# 467444_130_3_5-A.net
KiCad netlist of a schematic drawn in Altium Designer
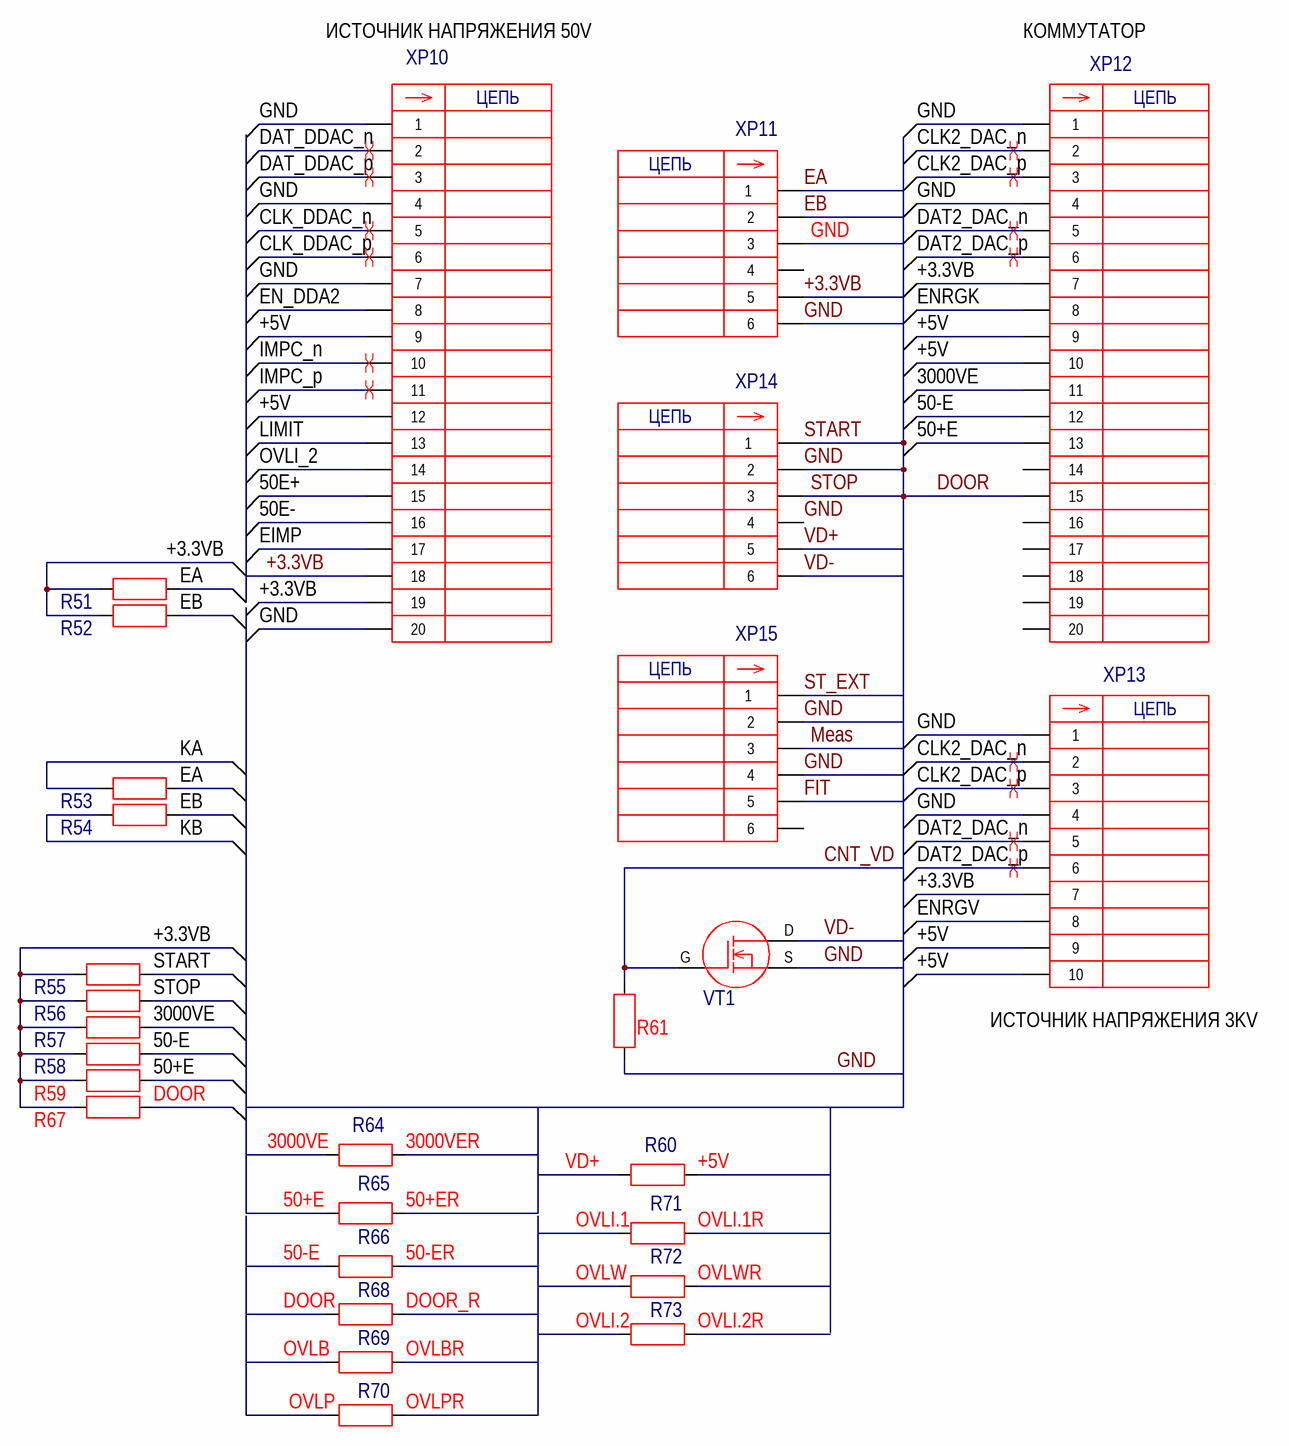
[diagram p0: УШЯИ.467444.130Э3_5-A.SchDoc]

(export (version "E")
  (design (tool "Eeschema 10.0.6"))
  (components
    (comp (ref "R51")
      (value "10k")
      (footprint "R_0805 [2012 Metric]")
      (fields (field (name "TOLERANCE") "±1%"))
      (libsource (lib "lib") (part "R_Const"))
    )
    (comp (ref "R52")
      (value "10k")
      (footprint "R_0805 [2012 Metric]")
      (fields (field (name "TOLERANCE") "±1%"))
      (libsource (lib "lib") (part "R_Const"))
    )
    (comp (ref "R53")
      (value "10k")
      (footprint "R_0805 [2012 Metric]")
      (fields (field (name "TOLERANCE") "±1%"))
      (libsource (lib "lib") (part "R_Const"))
    )
    (comp (ref "R54")
      (value "10k")
      (footprint "R_0805 [2012 Metric]")
      (fields (field (name "TOLERANCE") "±1%"))
      (libsource (lib "lib") (part "R_Const"))
    )
    (comp (ref "R55")
      (value "10k")
      (footprint "R_0805 [2012 Metric]")
      (fields (field (name "TOLERANCE") "±1%"))
      (libsource (lib "lib") (part "R_Const"))
    )
    (comp (ref "R56")
      (value "10k")
      (footprint "R_0805 [2012 Metric]")
      (fields (field (name "TOLERANCE") "±1%"))
      (libsource (lib "lib") (part "R_Const"))
    )
    (comp (ref "R57")
      (value "10k")
      (footprint "R_0805 [2012 Metric]")
      (fields (field (name "TOLERANCE") "±1%"))
      (libsource (lib "lib") (part "R_Const"))
    )
    (comp (ref "R58")
      (value "10k")
      (footprint "R_0805 [2012 Metric]")
      (fields (field (name "TOLERANCE") "±1%"))
      (libsource (lib "lib") (part "R_Const"))
    )
    (comp (ref "R59")
      (value "10k")
      (footprint "R_0805 [2012 Metric]")
      (fields (field (name "TOLERANCE") "±1%"))
      (libsource (lib "lib") (part "R_Const"))
    )
    (comp (ref "R60")
      (value "10k")
      (footprint "R_0805 [2012 Metric]")
      (fields (field (name "TOLERANCE") "±1%"))
      (libsource (lib "lib") (part "R_Const"))
    )
    (comp (ref "R61")
      (value "10k")
      (footprint "R_1206 [3216 Metric]")
      (fields (field (name "TOLERANCE") "±5%"))
      (libsource (lib "Lib_MN") (part "R_Const"))
    )
    (comp (ref "R64")
      (value "10k")
      (footprint "R_0805 [2012 Metric]")
      (fields (field (name "TOLERANCE") "±1%"))
      (libsource (lib "lib") (part "R_Const"))
    )
    (comp (ref "R65")
      (value "10k")
      (footprint "R_0805 [2012 Metric]")
      (fields (field (name "TOLERANCE") "±1%"))
      (libsource (lib "lib") (part "R_Const"))
    )
    (comp (ref "R66")
      (value "10k")
      (footprint "R_0805 [2012 Metric]")
      (fields (field (name "TOLERANCE") "±1%"))
      (libsource (lib "lib") (part "R_Const"))
    )
    (comp (ref "R67")
      (value "10k")
      (footprint "R_0805 [2012 Metric]")
      (fields (field (name "TOLERANCE") "±1%"))
      (libsource (lib "lib") (part "R_Const"))
    )
    (comp (ref "R68")
      (value "10k")
      (footprint "R_0805 [2012 Metric]")
      (fields (field (name "TOLERANCE") "±1%"))
      (libsource (lib "lib") (part "R_Const"))
    )
    (comp (ref "R69")
      (value "10k")
      (footprint "R_0805 [2012 Metric]")
      (fields (field (name "TOLERANCE") "±1%"))
      (libsource (lib "lib") (part "R_Const"))
    )
    (comp (ref "R70")
      (value "10k")
      (footprint "R_0805 [2012 Metric]")
      (fields (field (name "TOLERANCE") "±1%"))
      (libsource (lib "lib") (part "R_Const"))
    )
    (comp (ref "R71")
      (value "10k")
      (footprint "R_0805 [2012 Metric]")
      (fields (field (name "TOLERANCE") "±1%"))
      (libsource (lib "lib") (part "R_Const"))
    )
    (comp (ref "R72")
      (value "10k")
      (footprint "R_0805 [2012 Metric]")
      (fields (field (name "TOLERANCE") "±1%"))
      (libsource (lib "lib") (part "R_Const"))
    )
    (comp (ref "R73")
      (value "10k")
      (footprint "R_0805 [2012 Metric]")
      (fields (field (name "TOLERANCE") "±1%"))
      (libsource (lib "lib") (part "R_Const"))
    )
    (comp (ref "VT1")
      (value "NDS7002A")
      (footprint "SOT-23-3_[TO-236AB]_Transistor_n")
      (description "Транзистор n-канальный, изолированный затвор")
      (fields (field (name "MANUFACTURER") "Onsemi"))
      (libsource (lib "Lib_MN") (part "n-channel"))
    )
    (comp (ref "XP10")
      (value "BH2-20R")
      (footprint "BH2-20R")
      (description "Male, 20 pins, 2 rows, Right Angle, DS1014-20RF1B-B, 2 mm")
      (fields (field (name "MANUFACTURER") "Connfly electronic"))
      (libsource (lib "lib") (part "M_20"))
    )
    (comp (ref "XP11")
      (value "AMPMODU II 280372-2")
      (footprint "AMP II-280372-2")
      (description "Male, 6 pin, 1 row, Vertical, Board-to-Board, 2.54 mm")
      (fields (field (name "MANUFACTURER") "TE Connectivity"))
      (libsource (lib "Lib_MN") (part "M_6"))
    )
    (comp (ref "XP12")
      (value "BH2-20R")
      (footprint "BH2-20R")
      (description "Male, 20 pins, 2 rows, Right Angle, DS1014-20RF1B-B, 2 mm")
      (fields (field (name "MANUFACTURER") "Connfly electronic"))
      (libsource (lib "lib") (part "M_20"))
    )
    (comp (ref "XP13")
      (value "BH2-10R")
      (footprint "BH2-10R")
      (description "Male, 10 pins, 2 rows, Vertical, DS1014-10RF1B-B, 2 mm")
      (fields (field (name "MANUFACTURER") "Connfly electronic"))
      (libsource (lib "lib") (part "M_10"))
    )
    (comp (ref "XP14")
      (value "AMPMODU II 280372-2")
      (footprint "AMP II-280372-2")
      (description "Male, 6 pin, 1 row, Vertical, Board-to-Board, 2.54 mm")
      (fields (field (name "MANUFACTURER") "TE Connectivity"))
      (libsource (lib "Lib_MN") (part "M_6"))
    )
    (comp (ref "XP15")
      (value "AMPMODU II 280372-2")
      (footprint "AMP II-280372-2")
      (description "Male, 6 pin, 1 row, Vertical, Board-to-Board, 2.54 mm")
      (fields (field (name "MANUFACTURER") "TE Connectivity"))
      (libsource (lib "Lib_MN") (part "M_6"))
    )
  )
  (nets
    (net (code "1") (name "/+3.3VB") (class "Default")
      (node (ref "R51") (pin "1") (pinfunction "1_1") (pintype "passive"))
      (node (ref "R52") (pin "1") (pinfunction "1_1") (pintype "passive"))
      (node (ref "R55") (pin "1") (pinfunction "1_1") (pintype "passive"))
      (node (ref "R56") (pin "1") (pinfunction "1_1") (pintype "passive"))
      (node (ref "R57") (pin "1") (pinfunction "1_1") (pintype "passive"))
      (node (ref "R58") (pin "1") (pinfunction "1_1") (pintype "passive"))
      (node (ref "R59") (pin "1") (pinfunction "1_1") (pintype "passive"))
      (node (ref "R67") (pin "1") (pinfunction "1_1") (pintype "passive"))
      (node (ref "XP10") (pin "18") (pinfunction "18_18") (pintype "passive"))
      (node (ref "XP10") (pin "19") (pinfunction "19_19") (pintype "passive"))
      (node (ref "XP11") (pin "5") (pinfunction "5_5") (pintype "passive"))
      (node (ref "XP12") (pin "7") (pinfunction "7_7") (pintype "passive"))
      (node (ref "XP13") (pin "7") (pinfunction "7_7") (pintype "passive"))
    )
    (net (code "2") (name "/+5V") (class "Default")
      (node (ref "R60") (pin "2") (pinfunction "2_2") (pintype "passive"))
      (node (ref "XP10") (pin "12") (pinfunction "12_12") (pintype "passive"))
      (node (ref "XP10") (pin "9") (pinfunction "9_9") (pintype "passive"))
      (node (ref "XP12") (pin "10") (pinfunction "10_10") (pintype "passive"))
      (node (ref "XP12") (pin "9") (pinfunction "9_9") (pintype "passive"))
      (node (ref "XP13") (pin "10") (pinfunction "10_10") (pintype "passive"))
      (node (ref "XP13") (pin "9") (pinfunction "9_9") (pintype "passive"))
    )
    (net (code "3") (name "/50+E") (class "Default")
      (node (ref "R59") (pin "2") (pinfunction "2_2") (pintype "passive"))
      (node (ref "R65") (pin "1") (pinfunction "1_1") (pintype "passive"))
      (node (ref "XP12") (pin "13") (pinfunction "13_13") (pintype "passive"))
    )
    (net (code "4") (name "/50+ER") (class "Default")
      (node (ref "R65") (pin "2") (pinfunction "2_2") (pintype "passive"))
    )
    (net (code "5") (name "/50-E") (class "Default")
      (node (ref "R58") (pin "2") (pinfunction "2_2") (pintype "passive"))
      (node (ref "R66") (pin "1") (pinfunction "1_1") (pintype "passive"))
      (node (ref "XP12") (pin "12") (pinfunction "12_12") (pintype "passive"))
    )
    (net (code "6") (name "/50-ER") (class "Default")
      (node (ref "R66") (pin "2") (pinfunction "2_2") (pintype "passive"))
    )
    (net (code "7") (name "/50E+") (class "Default")
      (node (ref "XP10") (pin "15") (pinfunction "15_15") (pintype "passive"))
    )
    (net (code "8") (name "/50E-") (class "Default")
      (node (ref "XP10") (pin "16") (pinfunction "16_16") (pintype "passive"))
    )
    (net (code "9") (name "/3000VE") (class "Default")
      (node (ref "R57") (pin "2") (pinfunction "2_2") (pintype "passive"))
      (node (ref "R64") (pin "1") (pinfunction "1_1") (pintype "passive"))
      (node (ref "XP12") (pin "11") (pinfunction "11_11") (pintype "passive"))
    )
    (net (code "10") (name "/3000VER") (class "Default")
      (node (ref "R64") (pin "2") (pinfunction "2_2") (pintype "passive"))
    )
    (net (code "11") (name "/CLK2_DAC_n") (class "Default")
      (node (ref "XP12") (pin "2") (pinfunction "2_2") (pintype "passive"))
      (node (ref "XP13") (pin "2") (pinfunction "2_2") (pintype "passive"))
    )
    (net (code "12") (name "/CLK2_DAC_p") (class "Default")
      (node (ref "XP12") (pin "3") (pinfunction "3_3") (pintype "passive"))
      (node (ref "XP13") (pin "3") (pinfunction "3_3") (pintype "passive"))
    )
    (net (code "13") (name "/CLK_DDAC_n") (class "Default")
      (node (ref "XP10") (pin "5") (pinfunction "5_5") (pintype "passive"))
    )
    (net (code "14") (name "/CLK_DDAC_p") (class "Default")
      (node (ref "XP10") (pin "6") (pinfunction "6_6") (pintype "passive"))
    )
    (net (code "15") (name "/CNT_VD") (class "Default")
      (node (ref "R61") (pin "2") (pinfunction "2_2") (pintype "passive"))
      (node (ref "VT1") (pin "G") (pinfunction "З_G") (pintype "passive"))
    )
    (net (code "16") (name "/DAT2_DAC_n") (class "Default")
      (node (ref "XP12") (pin "5") (pinfunction "5_5") (pintype "passive"))
      (node (ref "XP13") (pin "5") (pinfunction "5_5") (pintype "passive"))
    )
    (net (code "17") (name "/DAT2_DAC_p") (class "Default")
      (node (ref "XP12") (pin "6") (pinfunction "6_6") (pintype "passive"))
      (node (ref "XP13") (pin "6") (pinfunction "6_6") (pintype "passive"))
    )
    (net (code "18") (name "/DAT_DDAC_n") (class "Default")
      (node (ref "XP10") (pin "2") (pinfunction "2_2") (pintype "passive"))
    )
    (net (code "19") (name "/DAT_DDAC_p") (class "Default")
      (node (ref "XP10") (pin "3") (pinfunction "3_3") (pintype "passive"))
    )
    (net (code "20") (name "/DOOR") (class "Default")
      (node (ref "R55") (pin "2") (pinfunction "2_2") (pintype "passive"))
      (node (ref "R56") (pin "2") (pinfunction "2_2") (pintype "passive"))
      (node (ref "R61") (pin "1") (pinfunction "1_1") (pintype "passive"))
      (node (ref "R67") (pin "2") (pinfunction "2_2") (pintype "passive"))
      (node (ref "R68") (pin "1") (pinfunction "1_1") (pintype "passive"))
      (node (ref "VT1") (pin "S") (pinfunction "И_S") (pintype "passive"))
      (node (ref "XP10") (pin "1") (pinfunction "1_1") (pintype "passive"))
      (node (ref "XP10") (pin "20") (pinfunction "20_20") (pintype "passive"))
      (node (ref "XP10") (pin "4") (pinfunction "4_4") (pintype "passive"))
      (node (ref "XP10") (pin "7") (pinfunction "7_7") (pintype "passive"))
      (node (ref "XP11") (pin "3") (pinfunction "3_3") (pintype "passive"))
      (node (ref "XP11") (pin "6") (pinfunction "6_6") (pintype "passive"))
      (node (ref "XP12") (pin "1") (pinfunction "1_1") (pintype "passive"))
      (node (ref "XP12") (pin "15") (pinfunction "15_15") (pintype "passive"))
      (node (ref "XP12") (pin "4") (pinfunction "4_4") (pintype "passive"))
      (node (ref "XP13") (pin "1") (pinfunction "1_1") (pintype "passive"))
      (node (ref "XP13") (pin "4") (pinfunction "4_4") (pintype "passive"))
      (node (ref "XP14") (pin "1") (pinfunction "1_1") (pintype "passive"))
      (node (ref "XP14") (pin "2") (pinfunction "2_2") (pintype "passive"))
      (node (ref "XP14") (pin "3") (pinfunction "3_3") (pintype "passive"))
      (node (ref "XP14") (pin "4") (pinfunction "4_4") (pintype "passive"))
      (node (ref "XP15") (pin "2") (pinfunction "2_2") (pintype "passive"))
      (node (ref "XP15") (pin "4") (pinfunction "4_4") (pintype "passive"))
    )
    (net (code "21") (name "/DOOR_R") (class "Default")
      (node (ref "R68") (pin "2") (pinfunction "2_2") (pintype "passive"))
    )
    (net (code "22") (name "/EA") (class "Default")
      (node (ref "R51") (pin "2") (pinfunction "2_2") (pintype "passive"))
      (node (ref "R53") (pin "2") (pinfunction "2_2") (pintype "passive"))
      (node (ref "XP11") (pin "1") (pinfunction "1_1") (pintype "passive"))
    )
    (net (code "23") (name "/EB") (class "Default")
      (node (ref "R52") (pin "2") (pinfunction "2_2") (pintype "passive"))
      (node (ref "R54") (pin "2") (pinfunction "2_2") (pintype "passive"))
      (node (ref "XP11") (pin "2") (pinfunction "2_2") (pintype "passive"))
    )
    (net (code "24") (name "/EIMP") (class "Default")
      (node (ref "XP10") (pin "17") (pinfunction "17_17") (pintype "passive"))
    )
    (net (code "25") (name "/ENRGK") (class "Default")
      (node (ref "XP12") (pin "8") (pinfunction "8_8") (pintype "passive"))
    )
    (net (code "26") (name "/ENRGV") (class "Default")
      (node (ref "XP13") (pin "8") (pinfunction "8_8") (pintype "passive"))
    )
    (net (code "27") (name "/EN_DDA2") (class "Default")
      (node (ref "XP10") (pin "8") (pinfunction "8_8") (pintype "passive"))
    )
    (net (code "28") (name "/FIT") (class "Default")
      (node (ref "XP15") (pin "5") (pinfunction "5_5") (pintype "passive"))
    )
    (net (code "29") (name "/IMPC_n") (class "Default")
      (node (ref "XP10") (pin "10") (pinfunction "10_10") (pintype "passive"))
    )
    (net (code "30") (name "/IMPC_p") (class "Default")
      (node (ref "XP10") (pin "11") (pinfunction "11_11") (pintype "passive"))
    )
    (net (code "31") (name "/KA") (class "Default")
      (node (ref "R53") (pin "1") (pinfunction "1_1") (pintype "passive"))
    )
    (net (code "32") (name "/KB") (class "Default")
      (node (ref "R54") (pin "1") (pinfunction "1_1") (pintype "passive"))
    )
    (net (code "33") (name "/LIMIT") (class "Default")
      (node (ref "XP10") (pin "13") (pinfunction "13_13") (pintype "passive"))
    )
    (net (code "34") (name "/Meas") (class "Default")
      (node (ref "XP15") (pin "3") (pinfunction "3_3") (pintype "passive"))
    )
    (net (code "35") (name "/OVLB") (class "Default")
      (node (ref "R69") (pin "1") (pinfunction "1_1") (pintype "passive"))
    )
    (net (code "36") (name "/OVLBR") (class "Default")
      (node (ref "R69") (pin "2") (pinfunction "2_2") (pintype "passive"))
    )
    (net (code "37") (name "/OVLI.1") (class "Default")
      (node (ref "R71") (pin "1") (pinfunction "1_1") (pintype "passive"))
    )
    (net (code "38") (name "/OVLI.1R") (class "Default")
      (node (ref "R71") (pin "2") (pinfunction "2_2") (pintype "passive"))
    )
    (net (code "39") (name "/OVLI.2") (class "Default")
      (node (ref "R73") (pin "1") (pinfunction "1_1") (pintype "passive"))
    )
    (net (code "40") (name "/OVLI.2R") (class "Default")
      (node (ref "R73") (pin "2") (pinfunction "2_2") (pintype "passive"))
    )
    (net (code "41") (name "/OVLI_2") (class "Default")
      (node (ref "XP10") (pin "14") (pinfunction "14_14") (pintype "passive"))
    )
    (net (code "42") (name "/OVLP") (class "Default")
      (node (ref "R70") (pin "1") (pinfunction "1_1") (pintype "passive"))
    )
    (net (code "43") (name "/OVLPR") (class "Default")
      (node (ref "R70") (pin "2") (pinfunction "2_2") (pintype "passive"))
    )
    (net (code "44") (name "/OVLW") (class "Default")
      (node (ref "R72") (pin "1") (pinfunction "1_1") (pintype "passive"))
    )
    (net (code "45") (name "/OVLWR") (class "Default")
      (node (ref "R72") (pin "2") (pinfunction "2_2") (pintype "passive"))
    )
    (net (code "46") (name "/ST_EXT") (class "Default")
      (node (ref "XP15") (pin "1") (pinfunction "1_1") (pintype "passive"))
    )
    (net (code "47") (name "/VD+") (class "Default")
      (node (ref "R60") (pin "1") (pinfunction "1_1") (pintype "passive"))
      (node (ref "XP14") (pin "5") (pinfunction "5_5") (pintype "passive"))
    )
    (net (code "48") (name "/VD-") (class "Default")
      (node (ref "VT1") (pin "D") (pinfunction "C_D") (pintype "passive"))
      (node (ref "XP14") (pin "6") (pinfunction "6_6") (pintype "passive"))
    )
    (net (code "49") (name "unconnected-(XP11-Pad4)") (class "Default")
      (node (ref "XP11") (pin "4") (pinfunction "4_4") (pintype "passive"))
    )
    (net (code "50") (name "unconnected-(XP12-Pad14)") (class "Default")
      (node (ref "XP12") (pin "14") (pinfunction "14_14") (pintype "passive"))
    )
    (net (code "51") (name "unconnected-(XP12-Pad16)") (class "Default")
      (node (ref "XP12") (pin "16") (pinfunction "16_16") (pintype "passive"))
    )
    (net (code "52") (name "unconnected-(XP12-Pad17)") (class "Default")
      (node (ref "XP12") (pin "17") (pinfunction "17_17") (pintype "passive"))
    )
    (net (code "53") (name "unconnected-(XP12-Pad18)") (class "Default")
      (node (ref "XP12") (pin "18") (pinfunction "18_18") (pintype "passive"))
    )
    (net (code "54") (name "unconnected-(XP12-Pad19)") (class "Default")
      (node (ref "XP12") (pin "19") (pinfunction "19_19") (pintype "passive"))
    )
    (net (code "55") (name "unconnected-(XP12-Pad20)") (class "Default")
      (node (ref "XP12") (pin "20") (pinfunction "20_20") (pintype "passive"))
    )
    (net (code "56") (name "unconnected-(XP15-Pad6)") (class "Default")
      (node (ref "XP15") (pin "6") (pinfunction "6_6") (pintype "passive"))
    )
  )
)
